# LightSensitiveDCPower.net
KiCad netlist of a schematic drawn in EAGLE
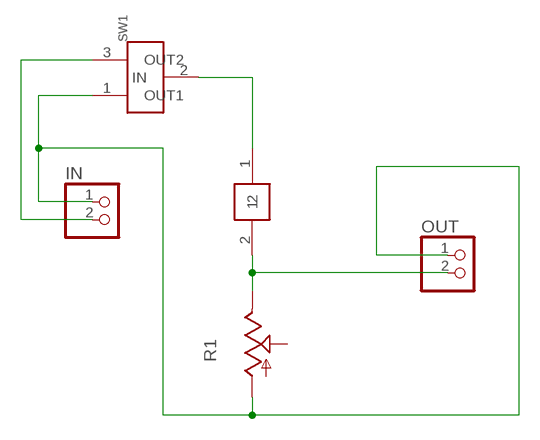
[diagram p0: schematic, sheet 1]

(export (version "E")
  (design (tool "Eeschema 10.0.6"))
  (components
    (comp (ref "IN")
      (value "PINHD-1X2")
      (footprint "eagle-import:1X02")
      (libsource (lib "eagle-import") (part "PINHD-1X2"))
    )
    (comp (ref "OUT")
      (value "PINHD-1X2")
      (footprint "eagle-import:1X02")
      (libsource (lib "eagle-import") (part "PINHD-1X2"))
    )
    (comp (ref "PC1")
      (value "PDV-P8101")
      (footprint "eagle-import:PHOTOCELL_CERAMIC")
      (libsource (lib "eagle-import") (part "PDV-P8101"))
    )
    (comp (ref "R1")
      (value "TRIM_US-B25P")
      (footprint "eagle-import:B25P")
      (libsource (lib "eagle-import") (part "TRIM_US-B25P"))
    )
    (comp (ref "SW1")
      (value "PCM12SMTR")
      (footprint "eagle-import:PCM12SMTR")
      (libsource (lib "eagle-import") (part "PCM12SMTR"))
    )
  )
  (nets
    (net (code "1") (name "Net-(OUT-Pad2)") (class "Default")
      (node (ref "OUT") (pin "2") (pinfunction "2_2") (pintype "passive"))
      (node (ref "PC1") (pin "2") (pinfunction "2_2") (pintype "bidirectional"))
      (node (ref "R1") (pin "E") (pinfunction "E_E") (pintype "passive"))
    )
    (net (code "2") (name "Net-(SW1-IN)") (class "Default")
      (node (ref "PC1") (pin "1") (pinfunction "1_1") (pintype "bidirectional"))
      (node (ref "SW1") (pin "2") (pinfunction "IN_2") (pintype "bidirectional"))
    )
    (net (code "3") (name "Net-(SW1-OUT1)") (class "Default")
      (node (ref "IN") (pin "1") (pinfunction "1_1") (pintype "passive"))
      (node (ref "OUT") (pin "1") (pinfunction "1_1") (pintype "passive"))
      (node (ref "R1") (pin "A") (pinfunction "A_A") (pintype "passive"))
      (node (ref "SW1") (pin "1") (pinfunction "OUT1_1") (pintype "bidirectional"))
    )
    (net (code "4") (name "Net-(SW1-OUT2)") (class "Default")
      (node (ref "IN") (pin "2") (pinfunction "2_2") (pintype "passive"))
      (node (ref "SW1") (pin "3") (pinfunction "OUT2_3") (pintype "bidirectional"))
    )
    (net (code "5") (name "unconnected-(R1-PadS)") (class "Default")
      (node (ref "R1") (pin "S") (pinfunction "S_S") (pintype "passive"))
    )
  )
)
